# Control_Buttons.net
KiCad netlist of a schematic drawn in Altium Designer
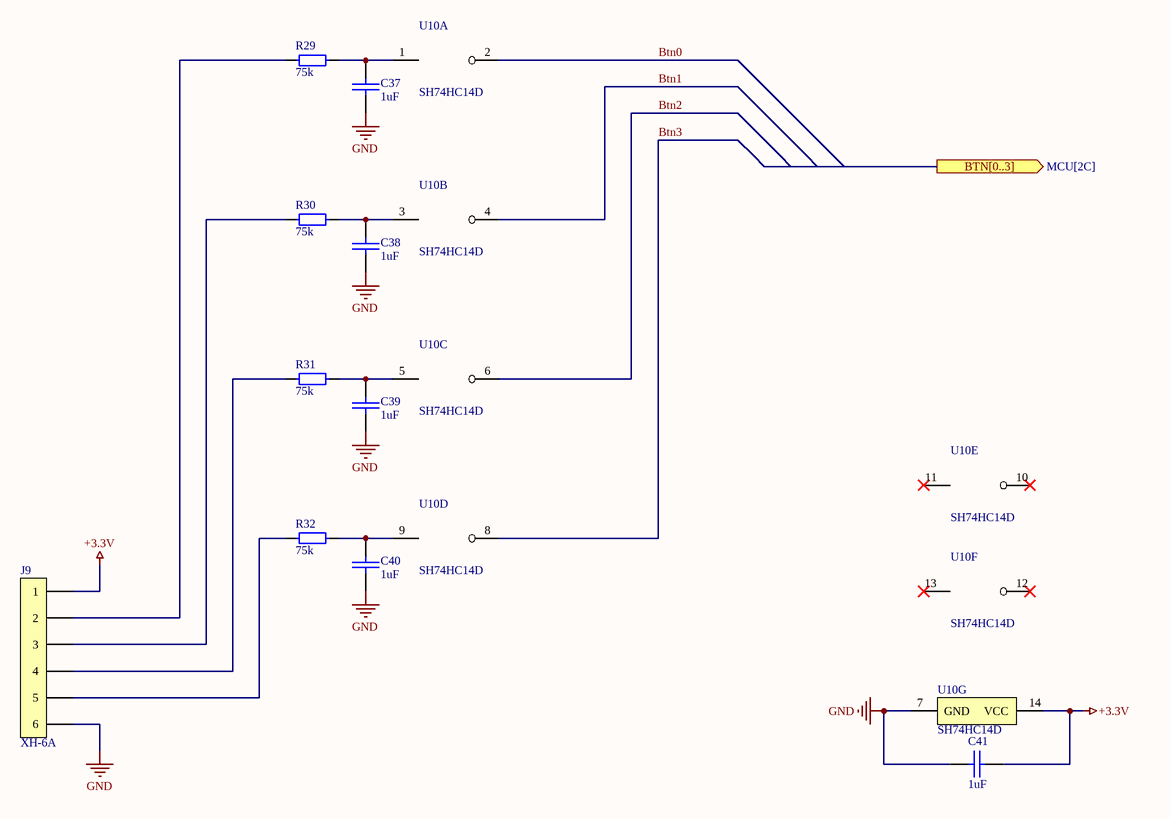
[diagram p0: Control Buttons.SchDoc]

(export (version "E")
  (design (tool "Eeschema 10.0.6"))
  (components
    (comp (ref "C37")
      (value "1uF")
      (footprint "0805 Capicator")
      (description "1uF X7R 10% 16V 0805")
      (fields
        (field (name "MANUFACTURER") "Murata Manufacturing")
        (field (name "PART NUMBER") "GRM21BR71C105KA01K")
      )
      (libsource (lib "BRT_Components") (part "Cap 1uF (0805)"))
    )
    (comp (ref "C38")
      (value "1uF")
      (footprint "0805 Capicator")
      (description "1uF X7R 10% 16V 0805")
      (fields
        (field (name "MANUFACTURER") "Murata Manufacturing")
        (field (name "PART NUMBER") "GRM21BR71C105KA01K")
      )
      (libsource (lib "BRT_Components") (part "Cap 1uF (0805)"))
    )
    (comp (ref "C39")
      (value "1uF")
      (footprint "0805 Capicator")
      (description "1uF X7R 10% 16V 0805")
      (fields
        (field (name "MANUFACTURER") "Murata Manufacturing")
        (field (name "PART NUMBER") "GRM21BR71C105KA01K")
      )
      (libsource (lib "BRT_Components") (part "Cap 1uF (0805)"))
    )
    (comp (ref "C40")
      (value "1uF")
      (footprint "0805 Capicator")
      (description "1uF X7R 10% 16V 0805")
      (fields
        (field (name "MANUFACTURER") "Murata Manufacturing")
        (field (name "PART NUMBER") "GRM21BR71C105KA01K")
      )
      (libsource (lib "BRT_Components") (part "Cap 1uF (0805)"))
    )
    (comp (ref "C41")
      (value "1uF")
      (footprint "0805 Capicator")
      (description "1uF X7R 10% 16V 0805")
      (fields
        (field (name "MANUFACTURER") "Murata Manufacturing")
        (field (name "PART NUMBER") "GRM21BR71C105KA01K")
      )
      (libsource (lib "BRT_Components") (part "Cap 1uF (0805)"))
    )
    (comp (ref "J9")
      (value "XH-6A")
      (footprint "CONN 1X6 (XH 2.54)")
      (description "Connector on the board straight 6pin 2.54mm")
      (libsource (lib "Altium_Library") (part "Connector XH-6A 2.54"))
    )
    (comp (ref "R29")
      (value "75k")
      (footprint "0805 Resistor")
      (description "0.125W 0805 75k, 1%")
      (fields (field (name "PART NUMBER") "RC0805FR-0775KL") (field (name "MANUFACTURER") "Taiwan"))
      (libsource (lib "BRT_Components") (part "Res 75k (0805)"))
    )
    (comp (ref "R30")
      (value "75k")
      (footprint "0805 Resistor")
      (description "0.125W 0805 75k, 1%")
      (fields (field (name "PART NUMBER") "RC0805FR-0775KL") (field (name "MANUFACTURER") "Taiwan"))
      (libsource (lib "BRT_Components") (part "Res 75k (0805)"))
    )
    (comp (ref "R31")
      (value "75k")
      (footprint "0805 Resistor")
      (description "0.125W 0805 75k, 1%")
      (fields (field (name "PART NUMBER") "RC0805FR-0775KL") (field (name "MANUFACTURER") "Taiwan"))
      (libsource (lib "BRT_Components") (part "Res 75k (0805)"))
    )
    (comp (ref "R32")
      (value "75k")
      (footprint "0805 Resistor")
      (description "0.125W 0805 75k, 1%")
      (fields (field (name "PART NUMBER") "RC0805FR-0775KL") (field (name "MANUFACTURER") "Taiwan"))
      (libsource (lib "BRT_Components") (part "Res 75k (0805)"))
    )
    (comp (ref "U10")
      (value "SH74HC14D")
      (footprint "SOIC-14")
      (description "SNx4HC14 Hex Schmitt-Trigger Inverters SOIC-14")
      (libsource (lib "Altium_Library") (part "Schmitt Trigger SN74HC14D"))
    )
  )
  (nets
    (net (code "5") (name "+3.3V") (class "Default")
      (node (ref "C41") (pin "1") (pinfunction "1_1") (pintype "passive"))
      (node (ref "J9") (pin "1") (pinfunction "1_1") (pintype "passive"))
      (node (ref "U10") (pin "14") (pinfunction "VCC_14") (pintype "power_in"))
    )
    (net (code "7") (name "/Btn0") (class "Default")
      (node (ref "U10") (pin "2") (pinfunction "1Y_2") (pintype "passive"))
    )
    (net (code "8") (name "/Btn1") (class "Default")
      (node (ref "U10") (pin "4") (pinfunction "2Y_4") (pintype "passive"))
    )
    (net (code "9") (name "/Btn2") (class "Default")
      (node (ref "U10") (pin "6") (pinfunction "3Y_6") (pintype "passive"))
    )
    (net (code "10") (name "/Btn3") (class "Default")
      (node (ref "U10") (pin "8") (pinfunction "4Y_8") (pintype "passive"))
    )
    (net (code "11") (name "GND") (class "Default")
      (node (ref "C37") (pin "1") (pinfunction "1_1") (pintype "passive"))
      (node (ref "C38") (pin "1") (pinfunction "1_1") (pintype "passive"))
      (node (ref "C39") (pin "1") (pinfunction "1_1") (pintype "passive"))
      (node (ref "C40") (pin "1") (pinfunction "1_1") (pintype "passive"))
      (node (ref "C41") (pin "2") (pinfunction "2_2") (pintype "passive"))
      (node (ref "J9") (pin "6") (pinfunction "6_6") (pintype "passive"))
      (node (ref "U10") (pin "7") (pinfunction "GND_7") (pintype "power_in"))
    )
    (net (code "12") (name "Net-(J9-Pad2)") (class "Default")
      (node (ref "J9") (pin "2") (pinfunction "2_2") (pintype "passive"))
      (node (ref "R29") (pin "1") (pinfunction "1_1") (pintype "passive"))
    )
    (net (code "13") (name "Net-(J9-Pad3)") (class "Default")
      (node (ref "J9") (pin "3") (pinfunction "3_3") (pintype "passive"))
      (node (ref "R30") (pin "1") (pinfunction "1_1") (pintype "passive"))
    )
    (net (code "14") (name "Net-(J9-Pad4)") (class "Default")
      (node (ref "J9") (pin "4") (pinfunction "4_4") (pintype "passive"))
      (node (ref "R31") (pin "1") (pinfunction "1_1") (pintype "passive"))
    )
    (net (code "15") (name "Net-(J9-Pad5)") (class "Default")
      (node (ref "J9") (pin "5") (pinfunction "5_5") (pintype "passive"))
      (node (ref "R32") (pin "1") (pinfunction "1_1") (pintype "passive"))
    )
    (net (code "16") (name "Net-(U10A-1A)") (class "Default")
      (node (ref "C37") (pin "2") (pinfunction "2_2") (pintype "passive"))
      (node (ref "R29") (pin "2") (pinfunction "2_2") (pintype "passive"))
      (node (ref "U10") (pin "1") (pinfunction "1A_1") (pintype "passive"))
    )
    (net (code "17") (name "Net-(U10B-2A)") (class "Default")
      (node (ref "C38") (pin "2") (pinfunction "2_2") (pintype "passive"))
      (node (ref "R30") (pin "2") (pinfunction "2_2") (pintype "passive"))
      (node (ref "U10") (pin "3") (pinfunction "2A_3") (pintype "passive"))
    )
    (net (code "18") (name "Net-(U10C-3A)") (class "Default")
      (node (ref "C39") (pin "2") (pinfunction "2_2") (pintype "passive"))
      (node (ref "R31") (pin "2") (pinfunction "2_2") (pintype "passive"))
      (node (ref "U10") (pin "5") (pinfunction "3A_5") (pintype "passive"))
    )
    (net (code "19") (name "Net-(U10D-4A)") (class "Default")
      (node (ref "C40") (pin "2") (pinfunction "2_2") (pintype "passive"))
      (node (ref "R32") (pin "2") (pinfunction "2_2") (pintype "passive"))
      (node (ref "U10") (pin "9") (pinfunction "4A_9") (pintype "passive"))
    )
    (net (code "20") (name "unconnected-(U10E-5A-Pad11)") (class "Default")
      (node (ref "U10") (pin "11") (pinfunction "5A_11") (pintype "passive+no_connect"))
    )
    (net (code "21") (name "unconnected-(U10E-5Y-Pad10)") (class "Default")
      (node (ref "U10") (pin "10") (pinfunction "5Y_10") (pintype "passive+no_connect"))
    )
    (net (code "22") (name "unconnected-(U10F-6A-Pad13)") (class "Default")
      (node (ref "U10") (pin "13") (pinfunction "6A_13") (pintype "passive+no_connect"))
    )
    (net (code "23") (name "unconnected-(U10F-6Y-Pad12)") (class "Default")
      (node (ref "U10") (pin "12") (pinfunction "6Y_12") (pintype "passive+no_connect"))
    )
  )
)
